# DSR_Altium_Schematic_NOTTESTED.net
KiCad netlist of a schematic drawn in Altium Designer
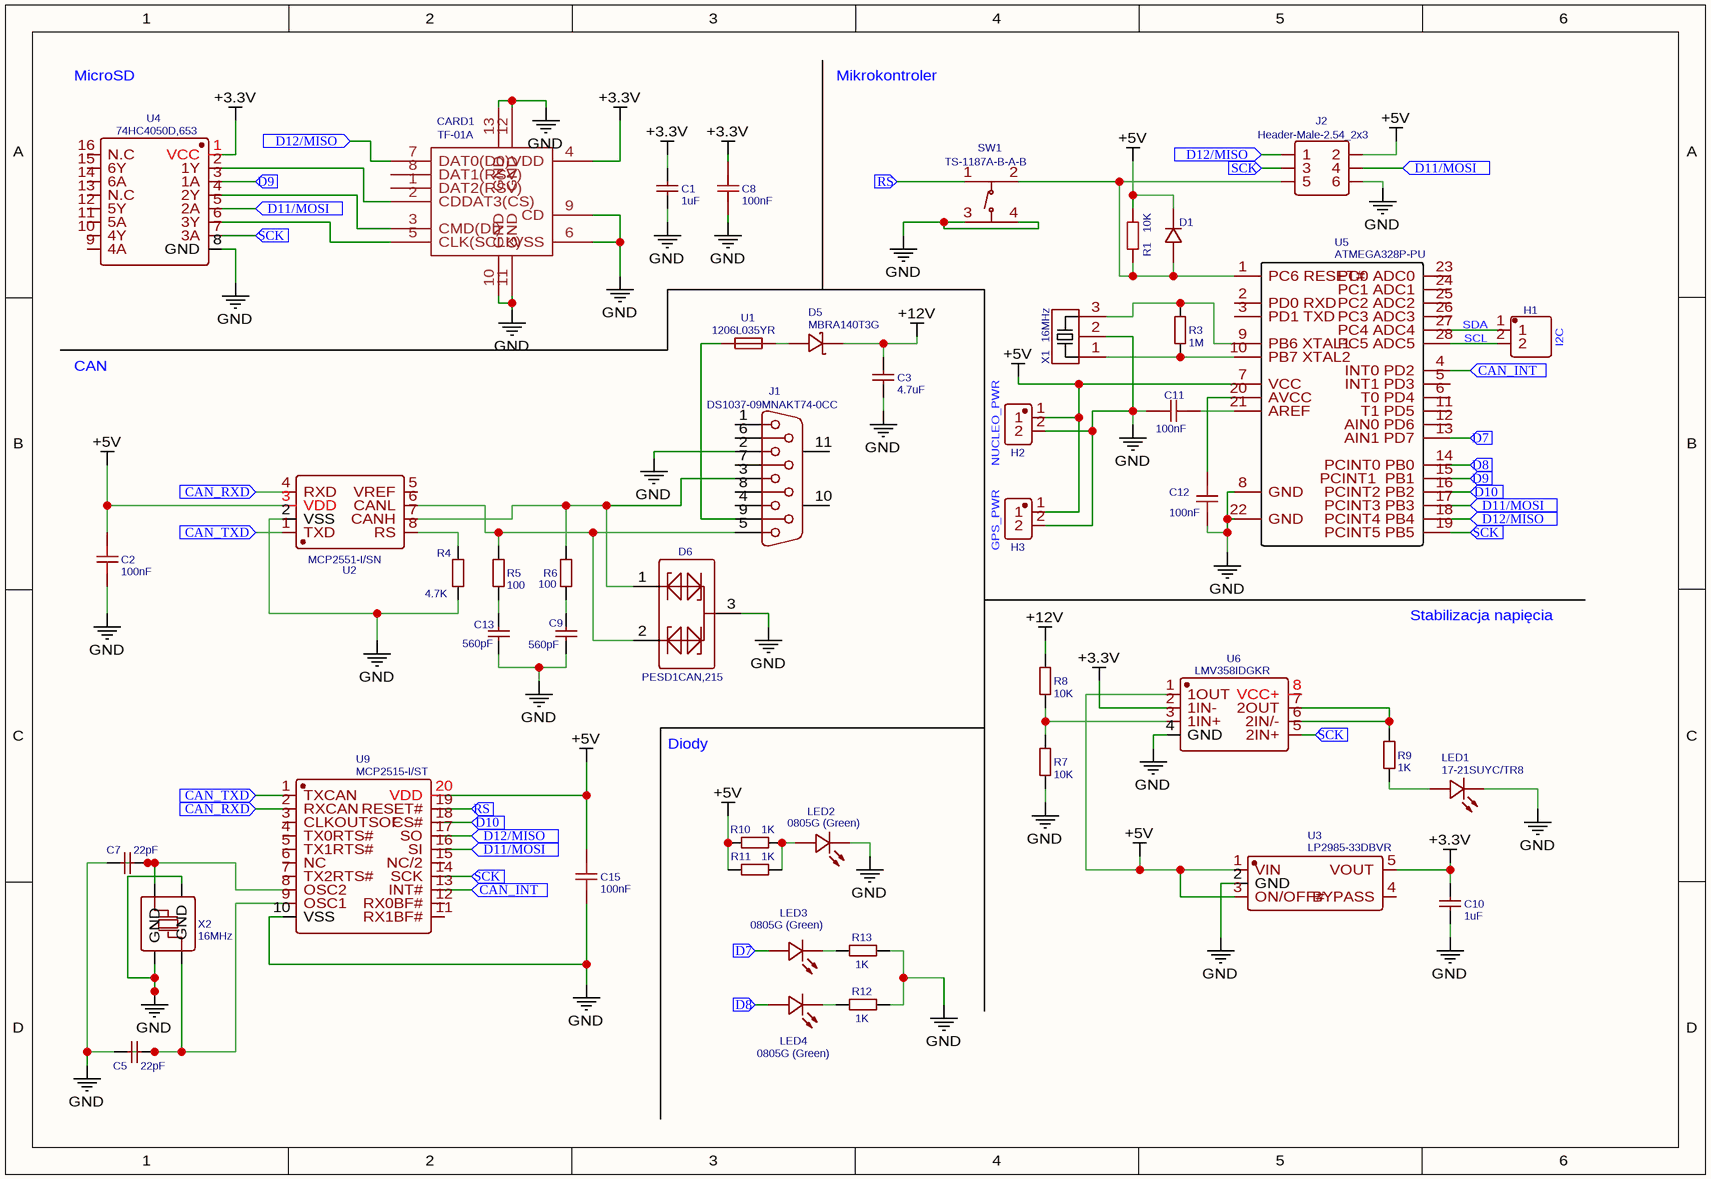
[diagram p0: DSR_Altium_Schematic_NOTTESTED.schdoc]

(export (version "E")
  (design (tool "Eeschema 10.0.6"))
  (components
    (comp (ref "C1")
      (value "1uF")
      (fields
        (field (name "BOM_MANUFACTURER PART") "CL10A105KB8NNNC")
        (field (name "BOM_SUPPLIER PART") "C15849")
      )
      (libsource (lib "altium-import") (part "root_1_1uF_"))
    )
    (comp (ref "C2")
      (value "100nF")
      (fields
        (field (name "BOM_MANUFACTURER PART") "CC0603KRX7R9BB104")
        (field (name "BOM_SUPPLIER PART") "C14663")
      )
      (libsource (lib "altium-import") (part "root_1_100nF_"))
    )
    (comp (ref "C3")
      (value "4.7uF")
      (fields
        (field (name "BOM_MANUFACTURER PART") "CL10A475KO8NNNC")
        (field (name "BOM_SUPPLIER PART") "C19666")
      )
      (libsource (lib "altium-import") (part "root_1_4.7uF_"))
    )
    (comp (ref "C5")
      (value "22pF")
      (fields
        (field (name "BOM_MANUFACTURER PART") "CL10C220JB8NNNC")
        (field (name "BOM_SUPPLIER PART") "C1653")
      )
      (libsource (lib "altium-import") (part "root_0_22pF_"))
    )
    (comp (ref "C7")
      (value "22pF")
      (fields
        (field (name "BOM_MANUFACTURER PART") "CL10C220JB8NNNC")
        (field (name "BOM_SUPPLIER PART") "C1653")
      )
      (libsource (lib "altium-import") (part "root_0_22pF_"))
    )
    (comp (ref "C8")
      (value "100nF")
      (fields
        (field (name "BOM_MANUFACTURER PART") "CC0603KRX7R9BB104")
        (field (name "BOM_SUPPLIER PART") "C14663")
      )
      (libsource (lib "altium-import") (part "root_1_100nF_"))
    )
    (comp (ref "C9")
      (value "560pF")
      (fields
        (field (name "BOM_MANUFACTURER PART") "CL10B561KB8NNNC")
        (field (name "BOM_SUPPLIER PART") "C84721")
      )
      (libsource (lib "altium-import") (part "root_1_560pF_"))
    )
    (comp (ref "C10")
      (value "1uF")
      (fields
        (field (name "BOM_MANUFACTURER PART") "CL10A105KB8NNNC")
        (field (name "BOM_SUPPLIER PART") "C15849")
      )
      (libsource (lib "altium-import") (part "root_1_1uF_"))
    )
    (comp (ref "C11")
      (value "100nF")
      (fields
        (field (name "BOM_MANUFACTURER PART") "CC0603KRX7R9BB104")
        (field (name "BOM_SUPPLIER PART") "C14663")
      )
      (libsource (lib "altium-import") (part "root_2_100nF_"))
    )
    (comp (ref "C12")
      (value "100nF")
      (fields
        (field (name "BOM_MANUFACTURER PART") "CC0603KRX7R9BB104")
        (field (name "BOM_SUPPLIER PART") "C14663")
      )
      (libsource (lib "altium-import") (part "root_1_100nF_"))
    )
    (comp (ref "C13")
      (value "560pF")
      (fields
        (field (name "BOM_MANUFACTURER PART") "CL10B561KB8NNNC")
        (field (name "BOM_SUPPLIER PART") "C84721")
      )
      (libsource (lib "altium-import") (part "root_1_560pF_"))
    )
    (comp (ref "C15")
      (value "100nF")
      (fields
        (field (name "BOM_MANUFACTURER PART") "CC0603KRX7R9BB104")
        (field (name "BOM_SUPPLIER PART") "C14663")
      )
      (libsource (lib "altium-import") (part "root_1_100nF_"))
    )
    (comp (ref "CARD1")
      (value "TF-01A")
      (fields (field (name "BOM_SUPPLIER PART") "C91145"))
      (libsource (lib "altium-import") (part "root_0_TF-01A_"))
    )
    (comp (ref "D1")
      (value "CD1206-S01575")
      (fields (field (name "BOM_SUPPLIER PART") "C75465") (field (name "CONTRIBUTOR") "LCSC"))
      (libsource (lib "altium-import") (part "root_3_CD1206-S01575_"))
    )
    (comp (ref "D5")
      (value "MBRA140T3G")
      (fields (field (name "BOM_SUPPLIER PART") "C54798") (field (name "CONTRIBUTOR") "LCSC"))
      (libsource (lib "altium-import") (part "root_2_MBRA140T3G_"))
    )
    (comp (ref "D6")
      (value "PESD1CAN,215")
      (fields (field (name "BOM_SUPPLIER PART") "C15771"))
      (libsource (lib "altium-import") (part "root_3_PESD1CAN,215_"))
    )
    (comp (ref "H1")
      (value "210S-1*2P L=11.6MMGold-plated black")
      (fields (field (name "BOM_SUPPLIER PART") "C124375") (field (name "CONTRIBUTOR") "LCSC"))
      (libsource (lib "altium-import") (part "root_0_210S-1*2P L=11.6MMGold-plated black_"))
    )
    (comp (ref "H2")
      (value "22850102ANG1SYA02")
      (fields (field (name "BOM_SUPPLIER PART") "C429966") (field (name "CONTRIBUTOR") "LCSC"))
      (libsource (lib "altium-import") (part "root_2_22850102ANG1SYA02_"))
    )
    (comp (ref "H3")
      (value "22850102ANG1SYA02")
      (fields (field (name "BOM_SUPPLIER PART") "C429966") (field (name "CONTRIBUTOR") "LCSC"))
      (libsource (lib "altium-import") (part "root_2_22850102ANG1SYA02_"))
    )
    (comp (ref "J1")
      (value "DS1037-09MNAKT74-0CC")
      (fields (field (name "BOM_SUPPLIER PART") "C75750"))
      (libsource (lib "altium-import") (part "root_1_DS1037-09MNAKT74-0CC_"))
    )
    (comp (ref "J2")
      (value "Header-Male-2.54_2x3")
      (fields (field (name "BOM_SUPPLIER PART") "C65114"))
      (libsource (lib "altium-import") (part "root_0_Header-Male-2.54_2x3_"))
    )
    (comp (ref "LED1")
      (value "17-21SUYC/TR8")
      (fields (field (name "BOM_SUPPLIER PART") "C2296"))
      (libsource (lib "altium-import") (part "root_2_17-21SUYC/TR8_"))
    )
    (comp (ref "LED2")
      (value "0805G (Green)")
      (fields (field (name "BOM_SUPPLIER PART") "C2297"))
      (libsource (lib "altium-import") (part "root_2_0805G (Green)_"))
    )
    (comp (ref "LED3")
      (value "0805G (Green)")
      (fields (field (name "BOM_SUPPLIER PART") "C2297"))
      (libsource (lib "altium-import") (part "root_2_0805G (Green)_"))
    )
    (comp (ref "LED4")
      (value "0805G (Green)")
      (fields (field (name "BOM_SUPPLIER PART") "C2297"))
      (libsource (lib "altium-import") (part "root_2_0805G (Green)_"))
    )
    (comp (ref "R1")
      (value "10K")
      (fields
        (field (name "BOM_SUPPLIER PART") "C269701")
        (field (name "BOM_MANUFACTURER PART") "RMC060310K1%N")
        (field (name "CONTRIBUTOR") "LCSC")
      )
      (libsource (lib "altium-import") (part "root_1_10K_"))
    )
    (comp (ref "R3")
      (value "1M")
      (fields
        (field (name "BOM_MANUFACTURER PART") "0603WAF1004T5E")
        (field (name "BOM_SUPPLIER PART") "C22935")
      )
      (libsource (lib "altium-import") (part "root_1_1M_"))
    )
    (comp (ref "R4")
      (value "4.7K")
      (fields
        (field (name "BOM_MANUFACTURER PART") "0603WAF4701T5E")
        (field (name "BOM_SUPPLIER PART") "C23162")
      )
      (libsource (lib "altium-import") (part "root_3_4.7K_"))
    )
    (comp (ref "R5")
      (value "100")
      (fields
        (field (name "BOM_MANUFACTURER PART") "0603WAF1000T5E")
        (field (name "BOM_SUPPLIER PART") "C22775")
      )
      (libsource (lib "altium-import") (part "root_1_100_"))
    )
    (comp (ref "R6")
      (value "100")
      (fields
        (field (name "BOM_MANUFACTURER PART") "0603WAF1000T5E")
        (field (name "BOM_SUPPLIER PART") "C22775")
      )
      (libsource (lib "altium-import") (part "root_1_100_"))
    )
    (comp (ref "R7")
      (value "10K")
      (fields
        (field (name "BOM_MANUFACTURER PART") "0603WAF1002T5E")
        (field (name "BOM_SUPPLIER PART") "C25804")
      )
      (libsource (lib "altium-import") (part "root_1_10K_"))
    )
    (comp (ref "R8")
      (value "10K")
      (fields
        (field (name "BOM_MANUFACTURER PART") "0603WAF1002T5E")
        (field (name "BOM_SUPPLIER PART") "C25804")
      )
      (libsource (lib "altium-import") (part "root_1_10K_"))
    )
    (comp (ref "R9")
      (value "1K")
      (fields
        (field (name "BOM_MANUFACTURER PART") "0603WAF1001T5E")
        (field (name "BOM_SUPPLIER PART") "C21190")
      )
      (libsource (lib "altium-import") (part "root_1_1K_"))
    )
    (comp (ref "R10")
      (value "1K")
      (fields
        (field (name "BOM_MANUFACTURER PART") "0603WAF1001T5E")
        (field (name "BOM_SUPPLIER PART") "C21190")
      )
      (libsource (lib "altium-import") (part "root_2_1K_"))
    )
    (comp (ref "R11")
      (value "1K")
      (fields
        (field (name "BOM_MANUFACTURER PART") "0603WAF1001T5E")
        (field (name "BOM_SUPPLIER PART") "C21190")
      )
      (libsource (lib "altium-import") (part "root_2_1K_"))
    )
    (comp (ref "R12")
      (value "1K")
      (fields
        (field (name "BOM_MANUFACTURER PART") "0603WAF1001T5E")
        (field (name "BOM_SUPPLIER PART") "C21190")
      )
      (libsource (lib "altium-import") (part "root_0_1K_"))
    )
    (comp (ref "R13")
      (value "1K")
      (fields
        (field (name "BOM_MANUFACTURER PART") "0603WAF1001T5E")
        (field (name "BOM_SUPPLIER PART") "C21190")
      )
      (libsource (lib "altium-import") (part "root_0_1K_"))
    )
    (comp (ref "SW1")
      (value "TS-1187A-B-A-B")
      (fields (field (name "BOM_SUPPLIER PART") "C318884") (field (name "CONTRIBUTOR") "LCSC"))
      (libsource (lib "altium-import") (part "root_0_TS-1187A-B-A-B_"))
    )
    (comp (ref "U1")
      (value "1206L035YR")
      (fields (field (name "BOM_SUPPLIER PART") "C99562"))
      (libsource (lib "altium-import") (part "root_0_1206L035YR_"))
    )
    (comp (ref "U2")
      (value "MCP2551-I/SN")
      (fields (field (name "BOM_SUPPLIER PART") "C7376"))
      (libsource (lib "altium-import") (part "root_0_MCP2551-I/SN_"))
    )
    (comp (ref "U3")
      (value "LP2985-33DBVR")
      (fields (field (name "BOM_SUPPLIER PART") "C95414"))
      (libsource (lib "altium-import") (part "root_0_LP2985-33DBVR_"))
    )
    (comp (ref "U4")
      (value "74HC4050D,653")
      (fields (field (name "BOM_SUPPLIER PART") "C43181"))
      (libsource (lib "altium-import") (part "root_0_74HC4050D,653_"))
    )
    (comp (ref "U5")
      (value "ATMEGA328P-PU")
      (fields (field (name "BOM_SUPPLIER PART") "C33901") (field (name "CONTRIBUTOR") "LCSC"))
      (libsource (lib "altium-import") (part "root_0_ATMEGA328P-PU_"))
    )
    (comp (ref "U6")
      (value "LMV358IDGKR")
      (fields (field (name "BOM_SUPPLIER PART") "C105242"))
      (libsource (lib "altium-import") (part "root_0_LMV358IDGKR_"))
    )
    (comp (ref "U9")
      (value "MCP2515-I/ST")
      (fields (field (name "BOM_SUPPLIER PART") "C15193"))
      (libsource (lib "altium-import") (part "root_0_MCP2515-I/ST_"))
    )
    (comp (ref "X1")
      (value "16MHz")
      (fields
        (field (name "BOM_MANUFACTURER PART") "CSTCE16M0V53-R0")
        (field (name "BOM_SUPPLIER PART") "C32180")
      )
      (libsource (lib "altium-import") (part "root_1_16MHz_"))
    )
    (comp (ref "X2")
      (value "16MHz")
      (fields
        (field (name "BOM_SUPPLIER PART") "C258963")
        (field (name "BOM_MANUFACTURER PART") "K16000J030")
        (field (name "CONTRIBUTOR") "LCSC")
      )
      (libsource (lib "") (part "root_1_16MHz__1"))
    )
  )
  (nets
    (net (code "1") (name "+3.3V") (class "Default")
      (node (ref "C1") (pin "2") (pinfunction "2_2") (pintype "passive"))
      (node (ref "C10") (pin "2") (pinfunction "2_2") (pintype "passive"))
      (node (ref "C8") (pin "2") (pinfunction "2_2") (pintype "passive"))
      (node (ref "CARD1") (pin "4") (pinfunction "VDD_4") (pintype "passive"))
      (node (ref "U3") (pin "5") (pinfunction "VOUT_5") (pintype "passive"))
      (node (ref "U4") (pin "1") (pinfunction "VCC_1") (pintype "passive"))
      (node (ref "U6") (pin "2") (pinfunction "1IN-_2") (pintype "passive"))
    )
    (net (code "2") (name "+5V") (class "Default")
      (node (ref "C15") (pin "2") (pinfunction "2_2") (pintype "passive"))
      (node (ref "C2") (pin "2") (pinfunction "2_2") (pintype "passive"))
      (node (ref "D1") (pin "1") (pinfunction "K_1") (pintype "passive"))
      (node (ref "H2") (pin "1") (pinfunction "1_1") (pintype "passive"))
      (node (ref "H3") (pin "1") (pinfunction "1_1") (pintype "passive"))
      (node (ref "J2") (pin "2") (pinfunction "2_2") (pintype "passive"))
      (node (ref "R1") (pin "2") (pinfunction "2_2") (pintype "passive"))
      (node (ref "R10") (pin "2") (pinfunction "2_2") (pintype "passive"))
      (node (ref "R11") (pin "2") (pinfunction "2_2") (pintype "passive"))
      (node (ref "U2") (pin "3") (pinfunction "VDD_3") (pintype "passive"))
      (node (ref "U3") (pin "1") (pinfunction "VIN_1") (pintype "passive"))
      (node (ref "U3") (pin "3") (pinfunction "ON/OFF#_3") (pintype "passive"))
      (node (ref "U5") (pin "7") (pinfunction "VCC_7") (pintype "passive"))
      (node (ref "U6") (pin "1") (pinfunction "1OUT_1") (pintype "passive"))
      (node (ref "U9") (pin "20") (pinfunction "VDD_20") (pintype "passive"))
    )
    (net (code "3") (name "+12V") (class "Default")
      (node (ref "C3") (pin "2") (pinfunction "2_2") (pintype "passive"))
      (node (ref "D5") (pin "1") (pinfunction "C_1") (pintype "passive"))
      (node (ref "R8") (pin "2") (pinfunction "2_2") (pintype "passive"))
    )
    (net (code "4") (name "/CAN_INT") (class "Default")
      (node (ref "U5") (pin "4") (pinfunction "INT0_PD2_4") (pintype "passive"))
      (node (ref "U9") (pin "13") (pinfunction "INT#_13") (pintype "passive"))
    )
    (net (code "5") (name "/CAN_RXD") (class "Default")
      (node (ref "U2") (pin "4") (pinfunction "RXD_4") (pintype "passive"))
      (node (ref "U9") (pin "2") (pinfunction "RXCAN_2") (pintype "passive"))
    )
    (net (code "6") (name "/CAN_TXD") (class "Default")
      (node (ref "U2") (pin "1") (pinfunction "TXD_1") (pintype "passive"))
      (node (ref "U9") (pin "1") (pinfunction "TXCAN_1") (pintype "passive"))
    )
    (net (code "7") (name "/D7") (class "Default")
      (node (ref "LED3") (pin "2") (pinfunction "A_2") (pintype "passive"))
      (node (ref "U5") (pin "13") (pinfunction "AIN1_PD7_13") (pintype "passive"))
    )
    (net (code "8") (name "/D8") (class "Default")
      (node (ref "LED4") (pin "2") (pinfunction "A_2") (pintype "passive"))
      (node (ref "U5") (pin "14") (pinfunction "PCINT0_PB0_14") (pintype "passive"))
    )
    (net (code "9") (name "/D9") (class "Default")
      (node (ref "U4") (pin "3") (pinfunction "1A_3") (pintype "passive"))
      (node (ref "U5") (pin "15") (pinfunction "PCINT1__PB1_15") (pintype "passive"))
    )
    (net (code "10") (name "/D10") (class "Default")
      (node (ref "U5") (pin "16") (pinfunction "PCINT2_PB2_16") (pintype "passive"))
      (node (ref "U9") (pin "18") (pinfunction "CS#_18") (pintype "passive"))
    )
    (net (code "11") (name "/D11{slash}MOSI") (class "Default")
      (node (ref "J2") (pin "4") (pinfunction "4_4") (pintype "passive"))
      (node (ref "U4") (pin "5") (pinfunction "2A_5") (pintype "passive"))
      (node (ref "U5") (pin "17") (pinfunction "PCINT3_PB3_17") (pintype "passive"))
      (node (ref "U9") (pin "16") (pinfunction "SI_16") (pintype "passive"))
    )
    (net (code "12") (name "/D12{slash}MISO") (class "Default")
      (node (ref "CARD1") (pin "7") (pinfunction "DAT0(D0)_7") (pintype "passive"))
      (node (ref "J2") (pin "1") (pinfunction "1_1") (pintype "passive"))
      (node (ref "U5") (pin "18") (pinfunction "PCINT4_PB4_18") (pintype "passive"))
      (node (ref "U9") (pin "17") (pinfunction "SO_17") (pintype "passive"))
    )
    (net (code "13") (name "/RS") (class "Default")
      (node (ref "SW1") (pin "1") (pinfunction "A_1") (pintype "passive"))
      (node (ref "U9") (pin "19") (pinfunction "RESET#_19") (pintype "passive"))
    )
    (net (code "14") (name "/SCK") (class "Default")
      (node (ref "J2") (pin "3") (pinfunction "3_3") (pintype "passive"))
      (node (ref "U4") (pin "7") (pinfunction "3A_7") (pintype "passive"))
      (node (ref "U5") (pin "19") (pinfunction "PCINT5_PB5_19") (pintype "passive"))
      (node (ref "U6") (pin "5") (pinfunction "2IN+_5") (pintype "passive"))
      (node (ref "U9") (pin "14") (pinfunction "SCK_14") (pintype "passive"))
    )
    (net (code "15") (name "GND") (class "Default")
      (node (ref "C1") (pin "1") (pinfunction "1_1") (pintype "passive"))
      (node (ref "C10") (pin "1") (pinfunction "1_1") (pintype "passive"))
      (node (ref "C11") (pin "2") (pinfunction "2_2") (pintype "passive"))
      (node (ref "C12") (pin "1") (pinfunction "1_1") (pintype "passive"))
      (node (ref "C13") (pin "1") (pinfunction "1_1") (pintype "passive"))
      (node (ref "C15") (pin "1") (pinfunction "1_1") (pintype "passive"))
      (node (ref "C2") (pin "1") (pinfunction "1_1") (pintype "passive"))
      (node (ref "C3") (pin "1") (pinfunction "1_1") (pintype "passive"))
      (node (ref "C5") (pin "1") (pinfunction "1_1") (pintype "passive"))
      (node (ref "C7") (pin "1") (pinfunction "1_1") (pintype "passive"))
      (node (ref "C8") (pin "1") (pinfunction "1_1") (pintype "passive"))
      (node (ref "C9") (pin "1") (pinfunction "1_1") (pintype "passive"))
      (node (ref "CARD1") (pin "10") (pinfunction "GND_10") (pintype "passive"))
      (node (ref "CARD1") (pin "11") (pinfunction "GND_11") (pintype "passive"))
      (node (ref "CARD1") (pin "12") (pinfunction "GND_12") (pintype "passive"))
      (node (ref "CARD1") (pin "13") (pinfunction "GND_13") (pintype "passive"))
      (node (ref "CARD1") (pin "6") (pinfunction "VSS_6") (pintype "passive"))
      (node (ref "CARD1") (pin "9") (pinfunction "CD_9") (pintype "passive"))
      (node (ref "D6") (pin "3") (pinfunction "3_3") (pintype "passive"))
      (node (ref "H2") (pin "2") (pinfunction "2_2") (pintype "passive"))
      (node (ref "H3") (pin "2") (pinfunction "2_2") (pintype "passive"))
      (node (ref "J1") (pin "2") (pinfunction "2_2") (pintype "passive"))
      (node (ref "J2") (pin "6") (pinfunction "6_6") (pintype "passive"))
      (node (ref "LED1") (pin "1") (pinfunction "-_1") (pintype "passive"))
      (node (ref "LED2") (pin "1") (pinfunction "K_1") (pintype "passive"))
      (node (ref "R12") (pin "2") (pinfunction "2_2") (pintype "passive"))
      (node (ref "R13") (pin "2") (pinfunction "2_2") (pintype "passive"))
      (node (ref "R4") (pin "2") (pinfunction "2_2") (pintype "passive"))
      (node (ref "R7") (pin "1") (pinfunction "1_1") (pintype "passive"))
      (node (ref "SW1") (pin "3") (pinfunction "C_3") (pintype "passive"))
      (node (ref "SW1") (pin "4") (pinfunction "D_4") (pintype "passive"))
      (node (ref "U2") (pin "2") (pinfunction "VSS_2") (pintype "passive"))
      (node (ref "U3") (pin "2") (pinfunction "GND_2") (pintype "passive"))
      (node (ref "U4") (pin "8") (pinfunction "GND_8") (pintype "passive"))
      (node (ref "U5") (pin "22") (pinfunction "GND_22") (pintype "passive"))
      (node (ref "U5") (pin "8") (pinfunction "GND_8") (pintype "passive"))
      (node (ref "U6") (pin "4") (pinfunction "GND_4") (pintype "passive"))
      (node (ref "U9") (pin "10") (pinfunction "VSS_10") (pintype "passive"))
      (node (ref "X1") (pin "2") (pinfunction "2_2") (pintype "passive"))
      (node (ref "X2") (pin "2") (pinfunction "GND_2") (pintype "passive"))
      (node (ref "X2") (pin "4") (pinfunction "GND_4") (pintype "passive"))
    )
    (net (code "16") (name "Net-(C9-Pad2)") (class "Default")
      (node (ref "C9") (pin "2") (pinfunction "2_2") (pintype "passive"))
      (node (ref "R6") (pin "1") (pinfunction "1_1") (pintype "passive"))
    )
    (net (code "17") (name "Net-(C13-Pad2)") (class "Default")
      (node (ref "C13") (pin "2") (pinfunction "2_2") (pintype "passive"))
      (node (ref "R5") (pin "1") (pinfunction "1_1") (pintype "passive"))
    )
    (net (code "18") (name "Net-(CARD1-CDDAT3(CS))") (class "Default")
      (node (ref "CARD1") (pin "2") (pinfunction "CDDAT3(CS)_2") (pintype "passive"))
      (node (ref "U4") (pin "2") (pinfunction "1Y_2") (pintype "passive"))
    )
    (net (code "19") (name "Net-(CARD1-CLK(SCLK))") (class "Default")
      (node (ref "CARD1") (pin "5") (pinfunction "CLK(SCLK)_5") (pintype "passive"))
      (node (ref "U4") (pin "6") (pinfunction "3Y_6") (pintype "passive"))
    )
    (net (code "20") (name "Net-(CARD1-CMD(DI))") (class "Default")
      (node (ref "CARD1") (pin "3") (pinfunction "CMD(DI)_3") (pintype "passive"))
      (node (ref "U4") (pin "4") (pinfunction "2Y_4") (pintype "passive"))
    )
    (net (code "21") (name "Net-(D1-A)") (class "Default")
      (node (ref "D1") (pin "2") (pinfunction "A_2") (pintype "passive"))
      (node (ref "J2") (pin "5") (pinfunction "5_5") (pintype "passive"))
      (node (ref "R1") (pin "1") (pinfunction "1_1") (pintype "passive"))
      (node (ref "SW1") (pin "2") (pinfunction "B_2") (pintype "passive"))
      (node (ref "U5") (pin "1") (pinfunction "PC6_RESET#_1") (pintype "passive"))
    )
    (net (code "22") (name "Net-(D5-A)") (class "Default")
      (node (ref "D5") (pin "2") (pinfunction "A_2") (pintype "passive"))
      (node (ref "U1") (pin "2") (pinfunction "2_2") (pintype "passive"))
    )
    (net (code "23") (name "Net-(J1-Pad9)") (class "Default")
      (node (ref "J1") (pin "9") (pinfunction "9_9") (pintype "passive"))
      (node (ref "U1") (pin "1") (pinfunction "1_1") (pintype "passive"))
    )
    (net (code "24") (name "Net-(LED1-+)") (class "Default")
      (node (ref "LED1") (pin "2") (pinfunction "+_2") (pintype "passive"))
      (node (ref "R9") (pin "1") (pinfunction "1_1") (pintype "passive"))
    )
    (net (code "25") (name "Net-(LED2-A)") (class "Default")
      (node (ref "LED2") (pin "2") (pinfunction "A_2") (pintype "passive"))
      (node (ref "R10") (pin "1") (pinfunction "1_1") (pintype "passive"))
      (node (ref "R11") (pin "1") (pinfunction "1_1") (pintype "passive"))
    )
    (net (code "26") (name "Net-(LED3-K)") (class "Default")
      (node (ref "LED3") (pin "1") (pinfunction "K_1") (pintype "passive"))
      (node (ref "R13") (pin "1") (pinfunction "1_1") (pintype "passive"))
    )
    (net (code "27") (name "Net-(LED4-K)") (class "Default")
      (node (ref "LED4") (pin "1") (pinfunction "K_1") (pintype "passive"))
      (node (ref "R12") (pin "1") (pinfunction "1_1") (pintype "passive"))
    )
    (net (code "28") (name "Net-(U2-CANH)") (class "Default")
      (node (ref "D6") (pin "1") (pinfunction "1_1") (pintype "passive"))
      (node (ref "J1") (pin "3") (pinfunction "3_3") (pintype "passive"))
      (node (ref "R6") (pin "2") (pinfunction "2_2") (pintype "passive"))
      (node (ref "U2") (pin "7") (pinfunction "CANH_7") (pintype "passive"))
    )
    (net (code "29") (name "Net-(U2-CANL)") (class "Default")
      (node (ref "D6") (pin "2") (pinfunction "2_2") (pintype "passive"))
      (node (ref "J1") (pin "5") (pinfunction "5_5") (pintype "passive"))
      (node (ref "R5") (pin "2") (pinfunction "2_2") (pintype "passive"))
      (node (ref "U2") (pin "6") (pinfunction "CANL_6") (pintype "passive"))
    )
    (net (code "30") (name "Net-(U2-RS)") (class "Default")
      (node (ref "R4") (pin "1") (pinfunction "1_1") (pintype "passive"))
      (node (ref "U2") (pin "8") (pinfunction "RS_8") (pintype "passive"))
    )
    (net (code "31") (name "Net-(U5-AREF)") (class "Default")
      (node (ref "C11") (pin "1") (pinfunction "1_1") (pintype "passive"))
      (node (ref "U5") (pin "21") (pinfunction "AREF_21") (pintype "passive"))
    )
    (net (code "32") (name "Net-(U5-AVCC)") (class "Default")
      (node (ref "C12") (pin "2") (pinfunction "2_2") (pintype "passive"))
      (node (ref "U5") (pin "20") (pinfunction "AVCC_20") (pintype "passive"))
    )
    (net (code "33") (name "Net-(U5-PB6_XTAL1)") (class "Default")
      (node (ref "R3") (pin "2") (pinfunction "2_2") (pintype "passive"))
      (node (ref "U5") (pin "9") (pinfunction "PB6_XTAL1_9") (pintype "passive"))
      (node (ref "X1") (pin "3") (pinfunction "3_3") (pintype "passive"))
    )
    (net (code "34") (name "Net-(U5-PB7_XTAL2)") (class "Default")
      (node (ref "R3") (pin "1") (pinfunction "1_1") (pintype "passive"))
      (node (ref "U5") (pin "10") (pinfunction "PB7_XTAL2_10") (pintype "passive"))
      (node (ref "X1") (pin "1") (pinfunction "1_1") (pintype "passive"))
    )
    (net (code "35") (name "Net-(U5-PC4_ADC4)") (class "Default")
      (node (ref "H1") (pin "1") (pinfunction "1_1") (pintype "passive"))
      (node (ref "U5") (pin "27") (pinfunction "PC4_ADC4_27") (pintype "passive"))
    )
    (net (code "36") (name "Net-(U5-PC5_ADC5)") (class "Default")
      (node (ref "H1") (pin "2") (pinfunction "2_2") (pintype "passive"))
      (node (ref "U5") (pin "28") (pinfunction "PC5_ADC5_28") (pintype "passive"))
    )
    (net (code "37") (name "Net-(U6-1IN+)") (class "Default")
      (node (ref "R7") (pin "2") (pinfunction "2_2") (pintype "passive"))
      (node (ref "R8") (pin "1") (pinfunction "1_1") (pintype "passive"))
      (node (ref "U6") (pin "3") (pinfunction "1IN+_3") (pintype "passive"))
    )
    (net (code "38") (name "Net-(U6-2IN{slash}-)") (class "Default")
      (node (ref "R9") (pin "2") (pinfunction "2_2") (pintype "passive"))
      (node (ref "U6") (pin "6") (pinfunction "2IN/-_6") (pintype "passive"))
      (node (ref "U6") (pin "7") (pinfunction "2OUT_7") (pintype "passive"))
    )
    (net (code "39") (name "Net-(U9-OSC1)") (class "Default")
      (node (ref "C5") (pin "2") (pinfunction "2_2") (pintype "passive"))
      (node (ref "U9") (pin "9") (pinfunction "OSC1_9") (pintype "passive"))
      (node (ref "X2") (pin "1") (pinfunction "OSC1_1") (pintype "passive"))
    )
    (net (code "40") (name "Net-(U9-OSC2)") (class "Default")
      (node (ref "C7") (pin "2") (pinfunction "2_2") (pintype "passive"))
      (node (ref "U9") (pin "8") (pinfunction "OSC2_8") (pintype "passive"))
      (node (ref "X2") (pin "3") (pinfunction "OSC2_3") (pintype "passive"))
    )
    (net (code "41") (name "unconnected-(CARD1-DAT1(RSV)-Pad8)") (class "Default")
      (node (ref "CARD1") (pin "8") (pinfunction "DAT1(RSV)_8") (pintype "passive"))
    )
    (net (code "42") (name "unconnected-(CARD1-DAT2(RSV)-Pad1)") (class "Default")
      (node (ref "CARD1") (pin "1") (pinfunction "DAT2(RSV)_1") (pintype "passive"))
    )
    (net (code "43") (name "unconnected-(J1-MH1-Pad10)") (class "Default")
      (node (ref "J1") (pin "10") (pinfunction "MH1_10") (pintype "passive"))
    )
    (net (code "44") (name "unconnected-(J1-MH2-Pad11)") (class "Default")
      (node (ref "J1") (pin "11") (pinfunction "MH2_11") (pintype "passive"))
    )
    (net (code "45") (name "unconnected-(J1-Pad1)") (class "Default")
      (node (ref "J1") (pin "1") (pinfunction "1_1") (pintype "passive"))
    )
    (net (code "46") (name "unconnected-(J1-Pad4)") (class "Default")
      (node (ref "J1") (pin "4") (pinfunction "4_4") (pintype "passive"))
    )
    (net (code "47") (name "unconnected-(J1-Pad6)") (class "Default")
      (node (ref "J1") (pin "6") (pinfunction "6_6") (pintype "passive"))
    )
    (net (code "48") (name "unconnected-(J1-Pad7)") (class "Default")
      (node (ref "J1") (pin "7") (pinfunction "7_7") (pintype "passive"))
    )
    (net (code "49") (name "unconnected-(J1-Pad8)") (class "Default")
      (node (ref "J1") (pin "8") (pinfunction "8_8") (pintype "passive"))
    )
    (net (code "50") (name "unconnected-(U2-VREF-Pad5)") (class "Default")
      (node (ref "U2") (pin "5") (pinfunction "VREF_5") (pintype "passive"))
    )
    (net (code "51") (name "unconnected-(U3-BYPASS-Pad4)") (class "Default")
      (node (ref "U3") (pin "4") (pinfunction "BYPASS_4") (pintype "passive"))
    )
    (net (code "52") (name "unconnected-(U4-4A-Pad9)") (class "Default")
      (node (ref "U4") (pin "9") (pinfunction "4A_9") (pintype "passive"))
    )
    (net (code "53") (name "unconnected-(U4-4Y-Pad10)") (class "Default")
      (node (ref "U4") (pin "10") (pinfunction "4Y_10") (pintype "passive"))
    )
    (net (code "54") (name "unconnected-(U4-5A-Pad11)") (class "Default")
      (node (ref "U4") (pin "11") (pinfunction "5A_11") (pintype "passive"))
    )
    (net (code "55") (name "unconnected-(U4-5Y-Pad12)") (class "Default")
      (node (ref "U4") (pin "12") (pinfunction "5Y_12") (pintype "passive"))
    )
    (net (code "56") (name "unconnected-(U4-6A-Pad14)") (class "Default")
      (node (ref "U4") (pin "14") (pinfunction "6A_14") (pintype "passive"))
    )
    (net (code "57") (name "unconnected-(U4-6Y-Pad15)") (class "Default")
      (node (ref "U4") (pin "15") (pinfunction "6Y_15") (pintype "passive"))
    )
    (net (code "58") (name "unconnected-(U4-N.C-Pad13)") (class "Default")
      (node (ref "U4") (pin "13") (pinfunction "N.C_13") (pintype "passive"))
    )
    (net (code "59") (name "unconnected-(U4-N.C-Pad16)") (class "Default")
      (node (ref "U4") (pin "16") (pinfunction "N.C_16") (pintype "passive"))
    )
    (net (code "60") (name "unconnected-(U5-AIN0_PD6-Pad12)") (class "Default")
      (node (ref "U5") (pin "12") (pinfunction "AIN0_PD6_12") (pintype "passive"))
    )
    (net (code "61") (name "unconnected-(U5-INT1_PD3-Pad5)") (class "Default")
      (node (ref "U5") (pin "5") (pinfunction "INT1_PD3_5") (pintype "passive"))
    )
    (net (code "62") (name "unconnected-(U5-PC0_ADC0-Pad23)") (class "Default")
      (node (ref "U5") (pin "23") (pinfunction "PC0_ADC0_23") (pintype "passive"))
    )
    (net (code "63") (name "unconnected-(U5-PC1_ADC1-Pad24)") (class "Default")
      (node (ref "U5") (pin "24") (pinfunction "PC1_ADC1_24") (pintype "passive"))
    )
    (net (code "64") (name "unconnected-(U5-PC2_ADC2-Pad25)") (class "Default")
      (node (ref "U5") (pin "25") (pinfunction "PC2_ADC2_25") (pintype "passive"))
    )
    (net (code "65") (name "unconnected-(U5-PC3_ADC3-Pad26)") (class "Default")
      (node (ref "U5") (pin "26") (pinfunction "PC3_ADC3_26") (pintype "passive"))
    )
    (net (code "66") (name "unconnected-(U5-PD0_RXD-Pad2)") (class "Default")
      (node (ref "U5") (pin "2") (pinfunction "PD0_RXD_2") (pintype "passive"))
    )
    (net (code "67") (name "unconnected-(U5-PD1_TXD-Pad3)") (class "Default")
      (node (ref "U5") (pin "3") (pinfunction "PD1_TXD_3") (pintype "passive"))
    )
    (net (code "68") (name "unconnected-(U5-T0_PD4-Pad6)") (class "Default")
      (node (ref "U5") (pin "6") (pinfunction "T0_PD4_6") (pintype "passive"))
    )
    (net (code "69") (name "unconnected-(U5-T1_PD5-Pad11)") (class "Default")
      (node (ref "U5") (pin "11") (pinfunction "T1_PD5_11") (pintype "passive"))
    )
    (net (code "70") (name "unconnected-(U6-VCC+-Pad8)") (class "Default")
      (node (ref "U6") (pin "8") (pinfunction "VCC+_8") (pintype "passive"))
    )
    (net (code "71") (name "unconnected-(U9-CLKOUTSOF-Pad3)") (class "Default")
      (node (ref "U9") (pin "3") (pinfunction "CLKOUTSOF_3") (pintype "passive"))
    )
    (net (code "72") (name "unconnected-(U9-NC-Pad6)") (class "Default")
      (node (ref "U9") (pin "6") (pinfunction "NC_6") (pintype "passive"))
    )
    (net (code "73") (name "unconnected-(U9-NC{slash}2-Pad15)") (class "Default")
      (node (ref "U9") (pin "15") (pinfunction "NC/2_15") (pintype "passive"))
    )
    (net (code "74") (name "unconnected-(U9-RX0BF#-Pad12)") (class "Default")
      (node (ref "U9") (pin "12") (pinfunction "RX0BF#_12") (pintype "passive"))
    )
    (net (code "75") (name "unconnected-(U9-RX1BF#-Pad11)") (class "Default")
      (node (ref "U9") (pin "11") (pinfunction "RX1BF#_11") (pintype "passive"))
    )
    (net (code "76") (name "unconnected-(U9-TX0RTS#-Pad4)") (class "Default")
      (node (ref "U9") (pin "4") (pinfunction "TX0RTS#_4") (pintype "passive"))
    )
    (net (code "77") (name "unconnected-(U9-TX1RTS#-Pad5)") (class "Default")
      (node (ref "U9") (pin "5") (pinfunction "TX1RTS#_5") (pintype "passive"))
    )
    (net (code "78") (name "unconnected-(U9-TX2RTS#-Pad7)") (class "Default")
      (node (ref "U9") (pin "7") (pinfunction "TX2RTS#_7") (pintype "passive"))
    )
  )
)
